# C-04_CPU_PWR.net
KiCad netlist of a schematic drawn in Altium Designer
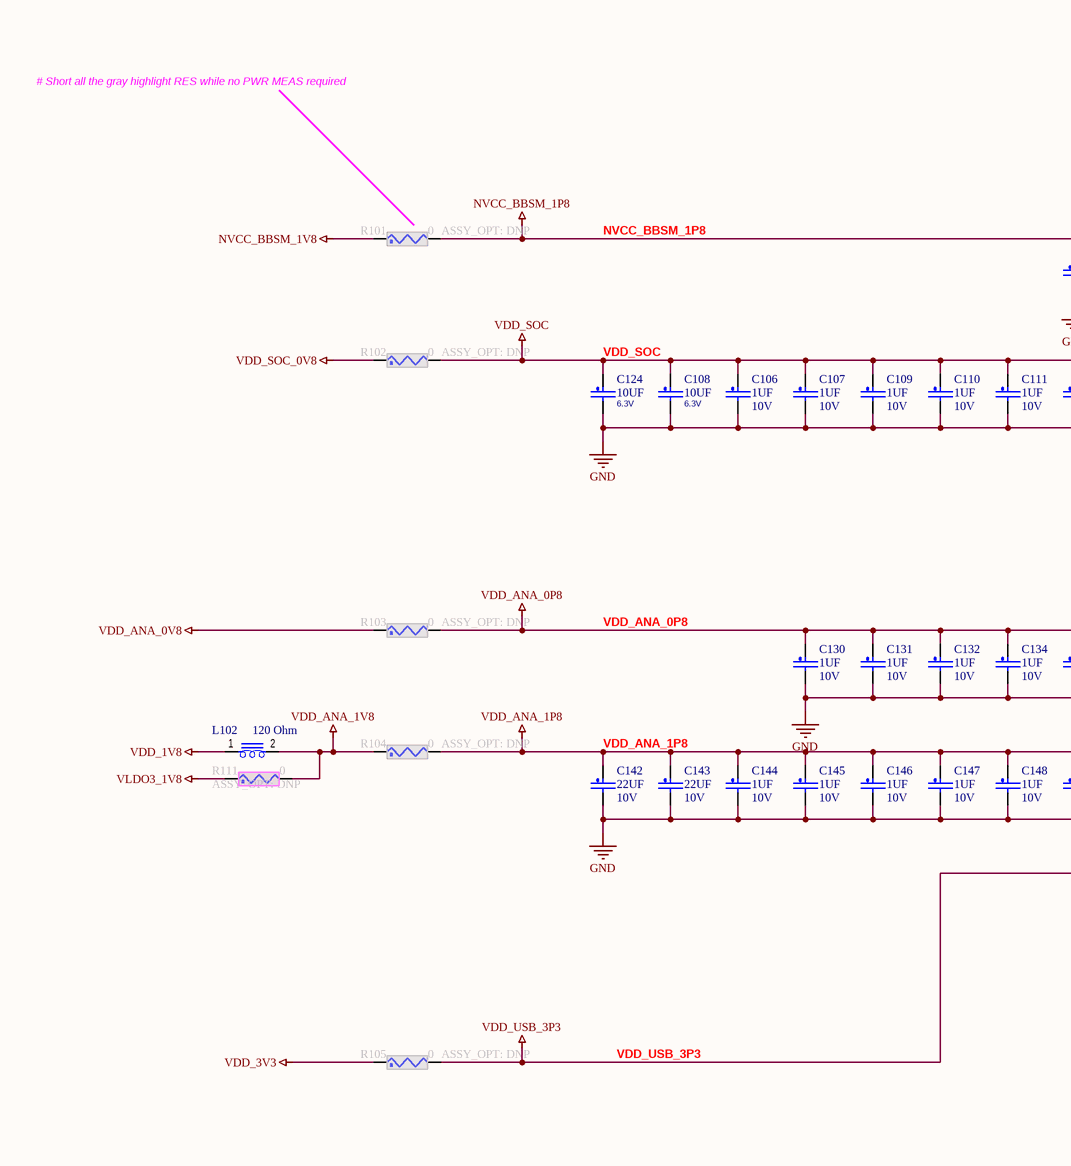
[diagram p0: C-04 CPU PWR.SchDoc, left]
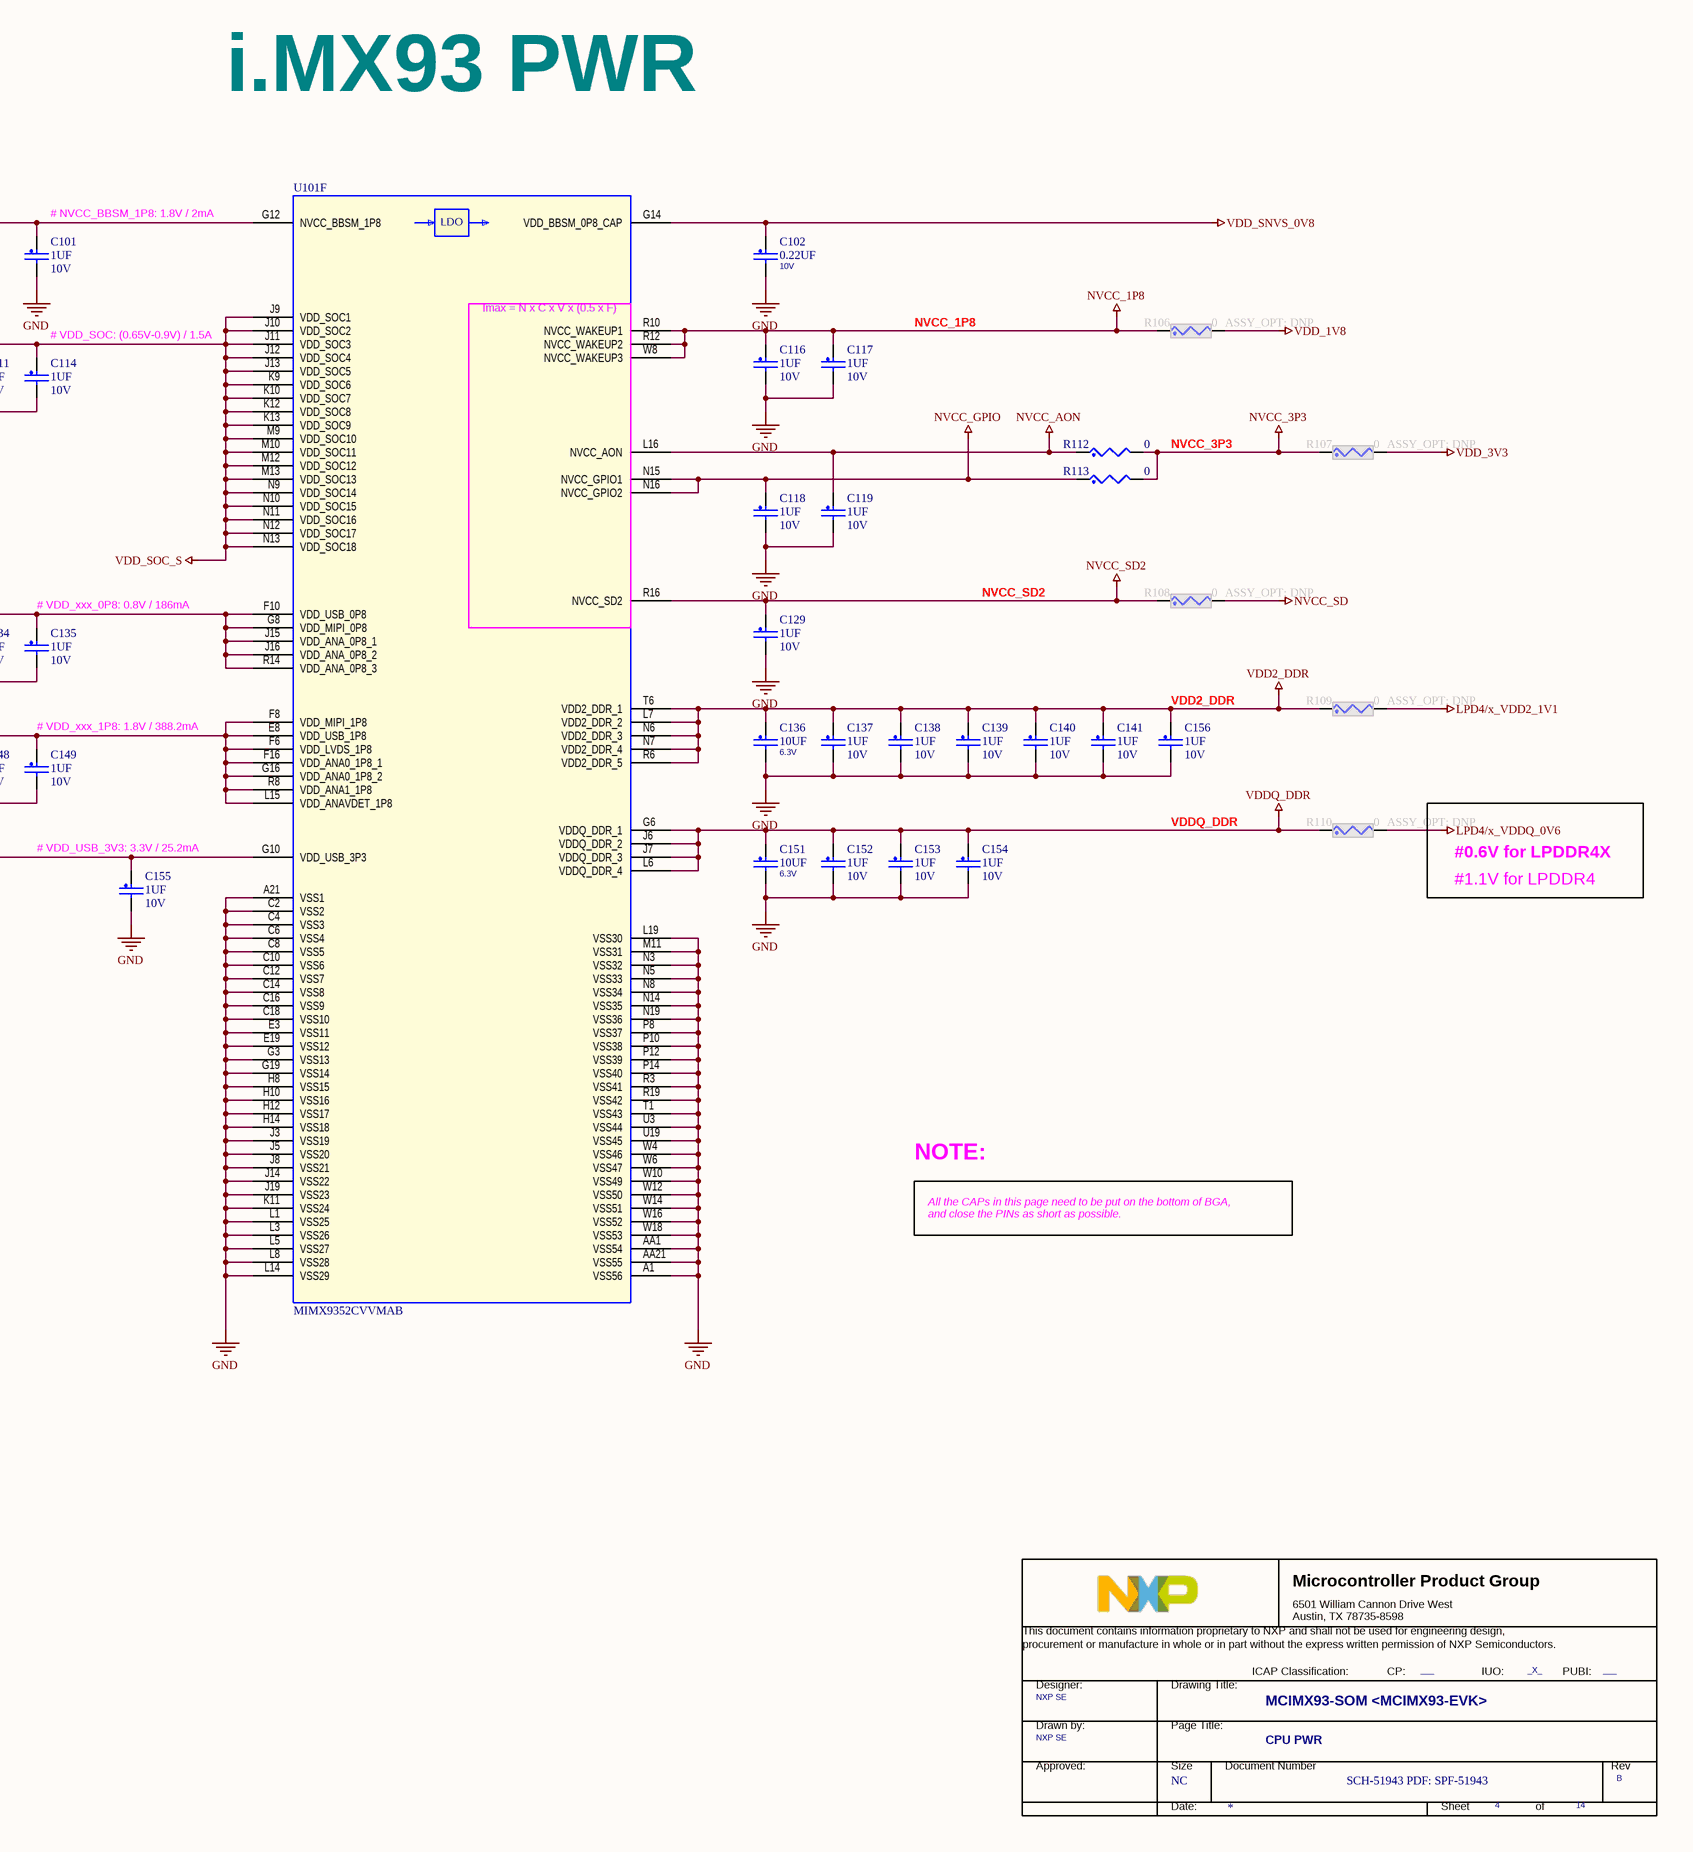
[diagram p1: C-04 CPU PWR.SchDoc, right]

(export (version "E")
  (design (tool "Eeschema 10.0.6"))
  (components
    (comp (ref "C101")
      (value "1UF")
      (footprint "0201_CC")
      (description "CAP CER 1.0uF 10V 10% X5R 0201")
      (fields (field (name "VOLTAGE") "10V") (field (name "TOLERANCE") "10%"))
      (libsource (lib "*") (part "CAP_NP"))
    )
    (comp (ref "C102")
      (value "0.22UF")
      (footprint "0201_CC")
      (description "CAP CER 0.22UF 10V 20% X5R 0201")
      (fields (field (name "TOLERANCE") "20%") (field (name "VOLTAGE") "10V"))
      (libsource (lib "*") (part "CAP_NP"))
    )
    (comp (ref "C106")
      (value "1UF")
      (footprint "0201_CC")
      (description "CAP CER 1.0uF 10V 10% X5R 0201")
      (fields (field (name "VOLTAGE") "10V") (field (name "TOLERANCE") "10%"))
      (libsource (lib "*") (part "CAP_NP"))
    )
    (comp (ref "C107")
      (value "1UF")
      (footprint "0201_CC")
      (description "CAP CER 1.0uF 10V 10% X5R 0201")
      (fields (field (name "VOLTAGE") "10V") (field (name "TOLERANCE") "10%"))
      (libsource (lib "*") (part "CAP_NP"))
    )
    (comp (ref "C108")
      (value "10UF")
      (footprint "0402_CC")
      (description "CAP CER 10UF 6.3V 20% X5R 0402")
      (fields (field (name "TOLERANCE") "20%") (field (name "VOLTAGE") "6.3V"))
      (libsource (lib "*") (part "CAP_NP"))
    )
    (comp (ref "C109")
      (value "1UF")
      (footprint "0201_CC")
      (description "CAP CER 1.0uF 10V 10% X5R 0201")
      (fields (field (name "VOLTAGE") "10V") (field (name "TOLERANCE") "10%"))
      (libsource (lib "*") (part "CAP_NP"))
    )
    (comp (ref "C110")
      (value "1UF")
      (footprint "0201_CC")
      (description "CAP CER 1.0uF 10V 10% X5R 0201")
      (fields (field (name "TOLERANCE") "10%") (field (name "VOLTAGE") "10V"))
      (libsource (lib "*") (part "CAP_NP"))
    )
    (comp (ref "C111")
      (value "1UF")
      (footprint "0201_CC")
      (description "CAP CER 1.0uF 10V 10% X5R 0201")
      (fields (field (name "TOLERANCE") "10%") (field (name "VOLTAGE") "10V"))
      (libsource (lib "*") (part "CAP_NP"))
    )
    (comp (ref "C114")
      (value "1UF")
      (footprint "0201_CC")
      (description "CAP CER 1.0uF 10V 10% X5R 0201")
      (fields (field (name "VOLTAGE") "10V") (field (name "TOLERANCE") "10%"))
      (libsource (lib "*") (part "CAP_NP"))
    )
    (comp (ref "C116")
      (value "1UF")
      (footprint "0201_CC")
      (description "CAP CER 1.0uF 10V 10% X5R 0201")
      (fields (field (name "VOLTAGE") "10V") (field (name "TOLERANCE") "10%"))
      (libsource (lib "*") (part "CAP_NP"))
    )
    (comp (ref "C117")
      (value "1UF")
      (footprint "0201_CC")
      (description "CAP CER 1.0uF 10V 10% X5R 0201")
      (fields (field (name "VOLTAGE") "10V") (field (name "TOLERANCE") "10%"))
      (libsource (lib "*") (part "CAP_NP"))
    )
    (comp (ref "C118")
      (value "1UF")
      (footprint "0201_CC")
      (description "CAP CER 1.0uF 10V 10% X5R 0201")
      (fields (field (name "VOLTAGE") "10V") (field (name "TOLERANCE") "10%"))
      (libsource (lib "*") (part "CAP_NP"))
    )
    (comp (ref "C119")
      (value "1UF")
      (footprint "0201_CC")
      (description "CAP CER 1.0uF 10V 10% X5R 0201")
      (fields (field (name "VOLTAGE") "10V") (field (name "TOLERANCE") "10%"))
      (libsource (lib "*") (part "CAP_NP"))
    )
    (comp (ref "C124")
      (value "10UF")
      (footprint "0402_CC")
      (description "CAP CER 10UF 6.3V 20% X5R 0402")
      (fields (field (name "TOLERANCE") "20%") (field (name "VOLTAGE") "6.3V"))
      (libsource (lib "*") (part "CAP_NP"))
    )
    (comp (ref "C129")
      (value "1UF")
      (footprint "0201_CC")
      (description "CAP CER 1.0uF 10V 10% X5R 0201")
      (fields (field (name "TOLERANCE") "10%") (field (name "VOLTAGE") "10V"))
      (libsource (lib "*") (part "CAP_NP"))
    )
    (comp (ref "C130")
      (value "1UF")
      (footprint "0201_CC")
      (description "CAP CER 1.0uF 10V 10% X5R 0201")
      (fields (field (name "VOLTAGE") "10V") (field (name "TOLERANCE") "10%"))
      (libsource (lib "*") (part "CAP_NP"))
    )
    (comp (ref "C131")
      (value "1UF")
      (footprint "0201_CC")
      (description "CAP CER 1.0uF 10V 10% X5R 0201")
      (fields (field (name "VOLTAGE") "10V") (field (name "TOLERANCE") "10%"))
      (libsource (lib "*") (part "CAP_NP"))
    )
    (comp (ref "C132")
      (value "1UF")
      (footprint "0201_CC")
      (description "CAP CER 1.0uF 10V 10% X5R 0201")
      (fields (field (name "VOLTAGE") "10V") (field (name "TOLERANCE") "10%"))
      (libsource (lib "*") (part "CAP_NP"))
    )
    (comp (ref "C134")
      (value "1UF")
      (footprint "0201_CC")
      (description "CAP CER 1.0uF 10V 10% X5R 0201")
      (fields (field (name "TOLERANCE") "10%") (field (name "VOLTAGE") "10V"))
      (libsource (lib "*") (part "CAP_NP"))
    )
    (comp (ref "C135")
      (value "1UF")
      (footprint "0201_CC")
      (description "CAP CER 1.0uF 10V 10% X5R 0201")
      (fields (field (name "TOLERANCE") "10%") (field (name "VOLTAGE") "10V"))
      (libsource (lib "*") (part "CAP_NP"))
    )
    (comp (ref "C136")
      (value "10UF")
      (footprint "0402_CC")
      (description "CAP CER 10UF 6.3V 20% X5R 0402")
      (fields (field (name "TOLERANCE") "20%") (field (name "VOLTAGE") "6.3V"))
      (libsource (lib "*") (part "CAP_NP"))
    )
    (comp (ref "C137")
      (value "1UF")
      (footprint "0201_CC")
      (description "CAP CER 1.0uF 10V 10% X5R 0201")
      (fields (field (name "TOLERANCE") "10%") (field (name "VOLTAGE") "10V"))
      (libsource (lib "*") (part "CAP_NP"))
    )
    (comp (ref "C138")
      (value "1UF")
      (footprint "0201_CC")
      (description "CAP CER 1.0uF 10V 10% X5R 0201")
      (fields (field (name "TOLERANCE") "10%") (field (name "VOLTAGE") "10V"))
      (libsource (lib "*") (part "CAP_NP"))
    )
    (comp (ref "C139")
      (value "1UF")
      (footprint "0201_CC")
      (description "CAP CER 1.0uF 10V 10% X5R 0201")
      (fields (field (name "TOLERANCE") "10%") (field (name "VOLTAGE") "10V"))
      (libsource (lib "*") (part "CAP_NP"))
    )
    (comp (ref "C140")
      (value "1UF")
      (footprint "0201_CC")
      (description "CAP CER 1.0uF 10V 10% X5R 0201")
      (fields (field (name "TOLERANCE") "10%") (field (name "VOLTAGE") "10V"))
      (libsource (lib "*") (part "CAP_NP"))
    )
    (comp (ref "C141")
      (value "1UF")
      (footprint "0201_CC")
      (description "CAP CER 1.0uF 10V 10% X5R 0201")
      (fields (field (name "TOLERANCE") "10%") (field (name "VOLTAGE") "10V"))
      (libsource (lib "*") (part "CAP_NP"))
    )
    (comp (ref "C142")
      (value "22UF")
      (footprint "CC0603")
      (description "CAP CER 22uF 10V 20% X5R 0603")
      (fields (field (name "VOLTAGE") "10V") (field (name "TOLERANCE") "20%"))
      (libsource (lib "*") (part "CAP_NP"))
    )
    (comp (ref "C143")
      (value "22UF")
      (footprint "CC0603")
      (description "CAP CER 22uF 10V 20% X5R 0603")
      (fields (field (name "TOLERANCE") "20%") (field (name "VOLTAGE") "10V"))
      (libsource (lib "*") (part "CAP_NP"))
    )
    (comp (ref "C144")
      (value "1UF")
      (footprint "0201_CC")
      (description "CAP CER 1.0uF 10V 10% X5R 0201")
      (fields (field (name "TOLERANCE") "10%") (field (name "VOLTAGE") "10V"))
      (libsource (lib "*") (part "CAP_NP"))
    )
    (comp (ref "C145")
      (value "1UF")
      (footprint "0201_CC")
      (description "CAP CER 1.0uF 10V 10% X5R 0201")
      (fields (field (name "VOLTAGE") "10V") (field (name "TOLERANCE") "10%"))
      (libsource (lib "*") (part "CAP_NP"))
    )
    (comp (ref "C146")
      (value "1UF")
      (footprint "0201_CC")
      (description "CAP CER 1.0uF 10V 10% X5R 0201")
      (fields (field (name "VOLTAGE") "10V") (field (name "TOLERANCE") "10%"))
      (libsource (lib "*") (part "CAP_NP"))
    )
    (comp (ref "C147")
      (value "1UF")
      (footprint "0201_CC")
      (description "CAP CER 1.0uF 10V 10% X5R 0201")
      (fields (field (name "TOLERANCE") "10%") (field (name "VOLTAGE") "10V"))
      (libsource (lib "*") (part "CAP_NP"))
    )
    (comp (ref "C148")
      (value "1UF")
      (footprint "0201_CC")
      (description "CAP CER 1.0uF 10V 10% X5R 0201")
      (fields (field (name "VOLTAGE") "10V") (field (name "TOLERANCE") "10%"))
      (libsource (lib "*") (part "CAP_NP"))
    )
    (comp (ref "C149")
      (value "1UF")
      (footprint "0201_CC")
      (description "CAP CER 1.0uF 10V 10% X5R 0201")
      (fields (field (name "VOLTAGE") "10V") (field (name "TOLERANCE") "10%"))
      (libsource (lib "*") (part "CAP_NP"))
    )
    (comp (ref "C151")
      (value "10UF")
      (footprint "0402_CC")
      (description "CAP CER 10UF 6.3V 20% X5R 0402")
      (fields (field (name "VOLTAGE") "6.3V") (field (name "TOLERANCE") "20%"))
      (libsource (lib "*") (part "CAP_NP"))
    )
    (comp (ref "C152")
      (value "1UF")
      (footprint "0201_CC")
      (description "CAP CER 1.0uF 10V 10% X5R 0201")
      (fields (field (name "VOLTAGE") "10V") (field (name "TOLERANCE") "10%"))
      (libsource (lib "*") (part "CAP_NP"))
    )
    (comp (ref "C153")
      (value "1UF")
      (footprint "0201_CC")
      (description "CAP CER 1.0uF 10V 10% X5R 0201")
      (fields (field (name "VOLTAGE") "10V") (field (name "TOLERANCE") "10%"))
      (libsource (lib "*") (part "CAP_NP"))
    )
    (comp (ref "C154")
      (value "1UF")
      (footprint "0201_CC")
      (description "CAP CER 1.0uF 10V 10% X5R 0201")
      (fields (field (name "VOLTAGE") "10V") (field (name "TOLERANCE") "10%"))
      (libsource (lib "*") (part "CAP_NP"))
    )
    (comp (ref "C155")
      (value "1UF")
      (footprint "0201_CC")
      (description "CAP CER 1.0uF 10V 10% X5R 0201")
      (fields (field (name "TOLERANCE") "10%") (field (name "VOLTAGE") "10V"))
      (libsource (lib "*") (part "CAP_NP"))
    )
    (comp (ref "C156")
      (value "1UF")
      (footprint "0201_CC")
      (description "CAP CER 1.0uF 10V 10% X5R 0201")
      (fields (field (name "VOLTAGE") "10V") (field (name "TOLERANCE") "10%"))
      (libsource (lib "*") (part "CAP_NP"))
    )
    (comp (ref "L102")
      (value "120 Ohm")
      (footprint "IND_0603")
      (description "IND FER BEAD 120OHM@100MHZ 2A 25% 0603")
      (libsource (lib "*") (part "BEAD_0"))
    )
    (comp (ref "R101")
      (value "0")
      (footprint "0402_CC")
      (description "RES MF ZERO OHM 1/16W 5% 0402")
      (fields
        (field (name "ASSY_OPT") "DNP")
        (field (name "TOLERANCE") "5%")
        (field (name "VOLTAGE") "1/16W")
      )
      (libsource (lib "*") (part "RES"))
    )
    (comp (ref "R102")
      (value "0")
      (footprint "RC0805_OV")
      (description "RES MF ZERO OHM 1/8W -- 0805")
      (fields (field (name "ASSY_OPT") "DNP") (field (name "TOLERANCE") "5%"))
      (libsource (lib "*") (part "RES"))
    )
    (comp (ref "R103")
      (value "0")
      (footprint "0603_CC")
      (description "RES MF ZERO OHM 1/10W -- 0603")
      (fields (field (name "ASSY_OPT") "DNP"))
      (libsource (lib "*") (part "RES"))
    )
    (comp (ref "R104")
      (value "0")
      (footprint "0603_CC")
      (description "RES MF ZERO OHM 1/10W -- 0603")
      (fields (field (name "ASSY_OPT") "DNP"))
      (libsource (lib "*") (part "RES"))
    )
    (comp (ref "R105")
      (value "0")
      (footprint "0402_CC")
      (description "RES MF ZERO OHM 1/16W 5% 0402")
      (fields
        (field (name "ASSY_OPT") "DNP")
        (field (name "TOLERANCE") "5%")
        (field (name "VOLTAGE") "1/16W")
      )
      (libsource (lib "*") (part "RES"))
    )
    (comp (ref "R106")
      (value "0")
      (footprint "0402_CC")
      (description "RES MF ZERO OHM 1/16W 5% 0402")
      (fields
        (field (name "ASSY_OPT") "DNP")
        (field (name "TOLERANCE") "5%")
        (field (name "VOLTAGE") "1/16W")
      )
      (libsource (lib "*") (part "RES"))
    )
    (comp (ref "R107")
      (value "0")
      (footprint "0402_CC")
      (description "RES MF ZERO OHM 1/16W 5% 0402")
      (fields
        (field (name "ASSY_OPT") "DNP")
        (field (name "TOLERANCE") "5%")
        (field (name "VOLTAGE") "1/16W")
      )
      (libsource (lib "*") (part "RES"))
    )
    (comp (ref "R108")
      (value "0")
      (footprint "0402_CC")
      (description "RES MF ZERO OHM 1/16W 5% 0402")
      (fields
        (field (name "ASSY_OPT") "DNP")
        (field (name "TOLERANCE") "5%")
        (field (name "VOLTAGE") "1/16W")
      )
      (libsource (lib "*") (part "RES"))
    )
    (comp (ref "R109")
      (value "0")
      (footprint "0603_CC")
      (description "RES MF ZERO OHM 1/10W -- 0603")
      (fields (field (name "ASSY_OPT") "DNP"))
      (libsource (lib "*") (part "RES"))
    )
    (comp (ref "R110")
      (value "0")
      (footprint "0603_CC")
      (description "RES MF ZERO OHM 1/10W -- 0603")
      (fields (field (name "ASSY_OPT") "DNP"))
      (libsource (lib "*") (part "RES"))
    )
    (comp (ref "R111")
      (value "0")
      (footprint "0603_CC")
      (description "RES MF ZERO OHM 1/10W -- 0603")
      (fields (field (name "ASSY_OPT") "DNP"))
      (libsource (lib "*") (part "RES"))
    )
    (comp (ref "R112")
      (value "0")
      (footprint "0402_CC")
      (description "RES MF ZERO OHM 1/16W 5% 0402")
      (fields (field (name "TOLERANCE") "5%") (field (name "VOLTAGE") "1/16W"))
      (libsource (lib "*") (part "RES"))
    )
    (comp (ref "R113")
      (value "0")
      (footprint "0402_CC")
      (description "RES MF ZERO OHM 1/16W 5% 0402")
      (fields (field (name "TOLERANCE") "5%") (field (name "VOLTAGE") "1/16W"))
      (libsource (lib "*") (part "RES"))
    )
    (comp (ref "U101")
      (value "MIMX9352CVVMAB")
      (footprint "SKT_BGA306_0P5_SQ16P23_ELAST")
      (description "SUBASSEMBLY SKT 306 BGA ELASTOMER SMT 0.5MM 395H AU + IC CPU 1.7GHz -- FCBGA306")
      (libsource (lib "*") (part "MIMX9352DVNxLAA"))
    )
  )
  (nets
    (net (code "1") (name "GND") (class "Default")
      (node (ref "C101") (pin "2") (pinfunction "2_2") (pintype "passive"))
      (node (ref "C102") (pin "2") (pinfunction "2_2") (pintype "passive"))
      (node (ref "C106") (pin "2") (pinfunction "2_2") (pintype "passive"))
      (node (ref "C107") (pin "2") (pinfunction "2_2") (pintype "passive"))
      (node (ref "C108") (pin "2") (pinfunction "2_2") (pintype "passive"))
      (node (ref "C109") (pin "2") (pinfunction "2_2") (pintype "passive"))
      (node (ref "C110") (pin "2") (pinfunction "2_2") (pintype "passive"))
      (node (ref "C111") (pin "2") (pinfunction "2_2") (pintype "passive"))
      (node (ref "C114") (pin "2") (pinfunction "2_2") (pintype "passive"))
      (node (ref "C116") (pin "2") (pinfunction "2_2") (pintype "passive"))
      (node (ref "C117") (pin "2") (pinfunction "2_2") (pintype "passive"))
      (node (ref "C118") (pin "2") (pinfunction "2_2") (pintype "passive"))
      (node (ref "C119") (pin "2") (pinfunction "2_2") (pintype "passive"))
      (node (ref "C124") (pin "2") (pinfunction "2_2") (pintype "passive"))
      (node (ref "C129") (pin "2") (pinfunction "2_2") (pintype "passive"))
      (node (ref "C130") (pin "2") (pinfunction "2_2") (pintype "passive"))
      (node (ref "C131") (pin "2") (pinfunction "2_2") (pintype "passive"))
      (node (ref "C132") (pin "2") (pinfunction "2_2") (pintype "passive"))
      (node (ref "C134") (pin "2") (pinfunction "2_2") (pintype "passive"))
      (node (ref "C135") (pin "2") (pinfunction "2_2") (pintype "passive"))
      (node (ref "C136") (pin "2") (pinfunction "2_2") (pintype "passive"))
      (node (ref "C137") (pin "2") (pinfunction "2_2") (pintype "passive"))
      (node (ref "C138") (pin "2") (pinfunction "2_2") (pintype "passive"))
      (node (ref "C139") (pin "2") (pinfunction "2_2") (pintype "passive"))
      (node (ref "C140") (pin "2") (pinfunction "2_2") (pintype "passive"))
      (node (ref "C141") (pin "2") (pinfunction "2_2") (pintype "passive"))
      (node (ref "C142") (pin "2") (pinfunction "2_2") (pintype "passive"))
      (node (ref "C143") (pin "2") (pinfunction "2_2") (pintype "passive"))
      (node (ref "C144") (pin "2") (pinfunction "2_2") (pintype "passive"))
      (node (ref "C145") (pin "2") (pinfunction "2_2") (pintype "passive"))
      (node (ref "C146") (pin "2") (pinfunction "2_2") (pintype "passive"))
      (node (ref "C147") (pin "2") (pinfunction "2_2") (pintype "passive"))
      (node (ref "C148") (pin "2") (pinfunction "2_2") (pintype "passive"))
      (node (ref "C149") (pin "2") (pinfunction "2_2") (pintype "passive"))
      (node (ref "C151") (pin "2") (pinfunction "2_2") (pintype "passive"))
      (node (ref "C152") (pin "2") (pinfunction "2_2") (pintype "passive"))
      (node (ref "C153") (pin "2") (pinfunction "2_2") (pintype "passive"))
      (node (ref "C154") (pin "2") (pinfunction "2_2") (pintype "passive"))
      (node (ref "C155") (pin "2") (pinfunction "2_2") (pintype "passive"))
      (node (ref "C156") (pin "2") (pinfunction "2_2") (pintype "passive"))
      (node (ref "U101") (pin "A1") (pinfunction "VSS56_A1") (pintype "passive"))
      (node (ref "U101") (pin "A21") (pinfunction "VSS1_A21") (pintype "passive"))
      (node (ref "U101") (pin "AA1") (pinfunction "VSS54_AA1") (pintype "passive"))
      (node (ref "U101") (pin "AA21") (pinfunction "VSS55_AA21") (pintype "passive"))
      (node (ref "U101") (pin "C10") (pinfunction "VSS6_C10") (pintype "passive"))
      (node (ref "U101") (pin "C12") (pinfunction "VSS7_C12") (pintype "passive"))
      (node (ref "U101") (pin "C14") (pinfunction "VSS8_C14") (pintype "passive"))
      (node (ref "U101") (pin "C16") (pinfunction "VSS9_C16") (pintype "passive"))
      (node (ref "U101") (pin "C18") (pinfunction "VSS10_C18") (pintype "passive"))
      (node (ref "U101") (pin "C2") (pinfunction "VSS2_C2") (pintype "passive"))
      (node (ref "U101") (pin "C4") (pinfunction "VSS3_C4") (pintype "passive"))
      (node (ref "U101") (pin "C6") (pinfunction "VSS4_C6") (pintype "passive"))
      (node (ref "U101") (pin "C8") (pinfunction "VSS5_C8") (pintype "passive"))
      (node (ref "U101") (pin "E19") (pinfunction "VSS12_E19") (pintype "passive"))
      (node (ref "U101") (pin "E3") (pinfunction "VSS11_E3") (pintype "passive"))
      (node (ref "U101") (pin "G19") (pinfunction "VSS14_G19") (pintype "passive"))
      (node (ref "U101") (pin "G3") (pinfunction "VSS13_G3") (pintype "passive"))
      (node (ref "U101") (pin "H10") (pinfunction "VSS16_H10") (pintype "passive"))
      (node (ref "U101") (pin "H12") (pinfunction "VSS17_H12") (pintype "passive"))
      (node (ref "U101") (pin "H14") (pinfunction "VSS18_H14") (pintype "passive"))
      (node (ref "U101") (pin "H8") (pinfunction "VSS15_H8") (pintype "passive"))
      (node (ref "U101") (pin "J14") (pinfunction "VSS22_J14") (pintype "passive"))
      (node (ref "U101") (pin "J19") (pinfunction "VSS23_J19") (pintype "passive"))
      (node (ref "U101") (pin "J3") (pinfunction "VSS19_J3") (pintype "passive"))
      (node (ref "U101") (pin "J5") (pinfunction "VSS20_J5") (pintype "passive"))
      (node (ref "U101") (pin "J8") (pinfunction "VSS21_J8") (pintype "passive"))
      (node (ref "U101") (pin "K11") (pinfunction "VSS24_K11") (pintype "passive"))
      (node (ref "U101") (pin "L1") (pinfunction "VSS25_L1") (pintype "passive"))
      (node (ref "U101") (pin "L14") (pinfunction "VSS29_L14") (pintype "passive"))
      (node (ref "U101") (pin "L19") (pinfunction "VSS30_L19") (pintype "passive"))
      (node (ref "U101") (pin "L3") (pinfunction "VSS26_L3") (pintype "passive"))
      (node (ref "U101") (pin "L5") (pinfunction "VSS27_L5") (pintype "passive"))
      (node (ref "U101") (pin "L8") (pinfunction "VSS28_L8") (pintype "passive"))
      (node (ref "U101") (pin "M11") (pinfunction "VSS31_M11") (pintype "passive"))
      (node (ref "U101") (pin "N14") (pinfunction "VSS35_N14") (pintype "passive"))
      (node (ref "U101") (pin "N19") (pinfunction "VSS36_N19") (pintype "passive"))
      (node (ref "U101") (pin "N3") (pinfunction "VSS32_N3") (pintype "passive"))
      (node (ref "U101") (pin "N5") (pinfunction "VSS33_N5") (pintype "passive"))
      (node (ref "U101") (pin "N8") (pinfunction "VSS34_N8") (pintype "passive"))
      (node (ref "U101") (pin "P10") (pinfunction "VSS38_P10") (pintype "passive"))
      (node (ref "U101") (pin "P12") (pinfunction "VSS39_P12") (pintype "passive"))
      (node (ref "U101") (pin "P14") (pinfunction "VSS40_P14") (pintype "passive"))
      (node (ref "U101") (pin "P8") (pinfunction "VSS37_P8") (pintype "passive"))
      (node (ref "U101") (pin "R19") (pinfunction "VSS42_R19") (pintype "passive"))
      (node (ref "U101") (pin "R3") (pinfunction "VSS41_R3") (pintype "passive"))
      (node (ref "U101") (pin "T1") (pinfunction "VSS43_T1") (pintype "passive"))
      (node (ref "U101") (pin "U19") (pinfunction "VSS45_U19") (pintype "passive"))
      (node (ref "U101") (pin "U3") (pinfunction "VSS44_U3") (pintype "passive"))
      (node (ref "U101") (pin "W10") (pinfunction "VSS49_W10") (pintype "passive"))
      (node (ref "U101") (pin "W12") (pinfunction "VSS50_W12") (pintype "passive"))
      (node (ref "U101") (pin "W14") (pinfunction "VSS51_W14") (pintype "passive"))
      (node (ref "U101") (pin "W16") (pinfunction "VSS52_W16") (pintype "passive"))
      (node (ref "U101") (pin "W18") (pinfunction "VSS53_W18") (pintype "passive"))
      (node (ref "U101") (pin "W4") (pinfunction "VSS46_W4") (pintype "passive"))
      (node (ref "U101") (pin "W6") (pinfunction "VSS47_W6") (pintype "passive"))
    )
    (net (code "2") (name "LPD4{slash}x_VDD2_1V1") (class "Default")
      (node (ref "R109") (pin "2") (pinfunction "2_2") (pintype "passive"))
    )
    (net (code "3") (name "LPD4{slash}x_VDDQ_0V6") (class "Default")
      (node (ref "R110") (pin "2") (pinfunction "2_2") (pintype "passive"))
    )
    (net (code "4") (name "NVCC_1P8") (class "Default")
      (node (ref "C116") (pin "1") (pinfunction "1_1") (pintype "passive"))
      (node (ref "C117") (pin "1") (pinfunction "1_1") (pintype "passive"))
      (node (ref "R106") (pin "1") (pinfunction "1_1") (pintype "passive"))
      (node (ref "U101") (pin "R10") (pinfunction "NVCC_WAKEUP1_R10") (pintype "passive"))
      (node (ref "U101") (pin "R12") (pinfunction "NVCC_WAKEUP2_R12") (pintype "passive"))
      (node (ref "U101") (pin "W8") (pinfunction "NVCC_WAKEUP3_W8") (pintype "passive"))
    )
    (net (code "5") (name "NVCC_3P3") (class "Default")
      (node (ref "R107") (pin "1") (pinfunction "1_1") (pintype "passive"))
      (node (ref "R112") (pin "2") (pinfunction "2_2") (pintype "passive"))
      (node (ref "R113") (pin "2") (pinfunction "2_2") (pintype "passive"))
    )
    (net (code "6") (name "NVCC_AON") (class "Default")
      (node (ref "C119") (pin "1") (pinfunction "1_1") (pintype "passive"))
      (node (ref "R112") (pin "1") (pinfunction "1_1") (pintype "passive"))
      (node (ref "U101") (pin "L16") (pinfunction "NVCC_AON_L16") (pintype "passive"))
    )
    (net (code "7") (name "NVCC_BBSM_1P8") (class "Default")
      (node (ref "C101") (pin "1") (pinfunction "1_1") (pintype "passive"))
      (node (ref "R101") (pin "2") (pinfunction "2_2") (pintype "passive"))
      (node (ref "U101") (pin "G12") (pinfunction "NVCC_BBSM_1P8_G12") (pintype "passive"))
    )
    (net (code "8") (name "NVCC_BBSM_1V8") (class "Default")
      (node (ref "R101") (pin "1") (pinfunction "1_1") (pintype "passive"))
    )
    (net (code "9") (name "NVCC_GPIO") (class "Default")
      (node (ref "C118") (pin "1") (pinfunction "1_1") (pintype "passive"))
      (node (ref "R113") (pin "1") (pinfunction "1_1") (pintype "passive"))
      (node (ref "U101") (pin "N15") (pinfunction "NVCC_GPIO1_N15") (pintype "passive"))
      (node (ref "U101") (pin "N16") (pinfunction "NVCC_GPIO2_N16") (pintype "passive"))
    )
    (net (code "10") (name "NVCC_SD") (class "Default")
      (node (ref "R108") (pin "2") (pinfunction "2_2") (pintype "passive"))
    )
    (net (code "11") (name "NVCC_SD2") (class "Default")
      (node (ref "C129") (pin "1") (pinfunction "1_1") (pintype "passive"))
      (node (ref "R108") (pin "1") (pinfunction "1_1") (pintype "passive"))
      (node (ref "U101") (pin "R16") (pinfunction "NVCC_SD2_R16") (pintype "passive"))
    )
    (net (code "12") (name "VDD2_DDR") (class "Default")
      (node (ref "C136") (pin "1") (pinfunction "1_1") (pintype "passive"))
      (node (ref "C137") (pin "1") (pinfunction "1_1") (pintype "passive"))
      (node (ref "C138") (pin "1") (pinfunction "1_1") (pintype "passive"))
      (node (ref "C139") (pin "1") (pinfunction "1_1") (pintype "passive"))
      (node (ref "C140") (pin "1") (pinfunction "1_1") (pintype "passive"))
      (node (ref "C141") (pin "1") (pinfunction "1_1") (pintype "passive"))
      (node (ref "C156") (pin "1") (pinfunction "1_1") (pintype "passive"))
      (node (ref "R109") (pin "1") (pinfunction "1_1") (pintype "passive"))
      (node (ref "U101") (pin "L7") (pinfunction "VDD2_DDR_2_L7") (pintype "passive"))
      (node (ref "U101") (pin "N6") (pinfunction "VDD2_DDR_3_N6") (pintype "passive"))
      (node (ref "U101") (pin "N7") (pinfunction "VDD2_DDR_4_N7") (pintype "passive"))
      (node (ref "U101") (pin "R6") (pinfunction "VDD2_DDR_5_R6") (pintype "passive"))
      (node (ref "U101") (pin "T6") (pinfunction "VDD2_DDR_1_T6") (pintype "passive"))
    )
    (net (code "13") (name "VDDQ_DDR") (class "Default")
      (node (ref "C151") (pin "1") (pinfunction "1_1") (pintype "passive"))
      (node (ref "C152") (pin "1") (pinfunction "1_1") (pintype "passive"))
      (node (ref "C153") (pin "1") (pinfunction "1_1") (pintype "passive"))
      (node (ref "C154") (pin "1") (pinfunction "1_1") (pintype "passive"))
      (node (ref "R110") (pin "1") (pinfunction "1_1") (pintype "passive"))
      (node (ref "U101") (pin "G6") (pinfunction "VDDQ_DDR_1_G6") (pintype "passive"))
      (node (ref "U101") (pin "J6") (pinfunction "VDDQ_DDR_2_J6") (pintype "passive"))
      (node (ref "U101") (pin "J7") (pinfunction "VDDQ_DDR_3_J7") (pintype "passive"))
      (node (ref "U101") (pin "L6") (pinfunction "VDDQ_DDR_4_L6") (pintype "passive"))
    )
    (net (code "14") (name "VDD_1V8") (class "Default")
      (node (ref "L102") (pin "1") (pinfunction "1_1") (pintype "passive"))
      (node (ref "R106") (pin "2") (pinfunction "2_2") (pintype "passive"))
    )
    (net (code "15") (name "VDD_3V3") (class "Default")
      (node (ref "R105") (pin "1") (pinfunction "1_1") (pintype "passive"))
      (node (ref "R107") (pin "2") (pinfunction "2_2") (pintype "passive"))
    )
    (net (code "16") (name "VDD_ANA_0P8") (class "Default")
      (node (ref "C130") (pin "1") (pinfunction "1_1") (pintype "passive"))
      (node (ref "C131") (pin "1") (pinfunction "1_1") (pintype "passive"))
      (node (ref "C132") (pin "1") (pinfunction "1_1") (pintype "passive"))
      (node (ref "C134") (pin "1") (pinfunction "1_1") (pintype "passive"))
      (node (ref "C135") (pin "1") (pinfunction "1_1") (pintype "passive"))
      (node (ref "R103") (pin "2") (pinfunction "2_2") (pintype "passive"))
      (node (ref "U101") (pin "F10") (pinfunction "VDD_USB_0P8_F10") (pintype "passive"))
      (node (ref "U101") (pin "G8") (pinfunction "VDD_MIPI_0P8_G8") (pintype "passive"))
      (node (ref "U101") (pin "J15") (pinfunction "VDD_ANA_0P8_1_J15") (pintype "passive"))
      (node (ref "U101") (pin "J16") (pinfunction "VDD_ANA_0P8_2_J16") (pintype "passive"))
      (node (ref "U101") (pin "R14") (pinfunction "VDD_ANA_0P8_3_R14") (pintype "passive"))
    )
    (net (code "17") (name "VDD_ANA_0V8") (class "Default")
      (node (ref "R103") (pin "1") (pinfunction "1_1") (pintype "passive"))
    )
    (net (code "18") (name "VDD_ANA_1P8") (class "Default")
      (node (ref "C142") (pin "1") (pinfunction "1_1") (pintype "passive"))
      (node (ref "C143") (pin "1") (pinfunction "1_1") (pintype "passive"))
      (node (ref "C144") (pin "1") (pinfunction "1_1") (pintype "passive"))
      (node (ref "C145") (pin "1") (pinfunction "1_1") (pintype "passive"))
      (node (ref "C146") (pin "1") (pinfunction "1_1") (pintype "passive"))
      (node (ref "C147") (pin "1") (pinfunction "1_1") (pintype "passive"))
      (node (ref "C148") (pin "1") (pinfunction "1_1") (pintype "passive"))
      (node (ref "C149") (pin "1") (pinfunction "1_1") (pintype "passive"))
      (node (ref "R104") (pin "2") (pinfunction "2_2") (pintype "passive"))
      (node (ref "U101") (pin "E8") (pinfunction "VDD_USB_1P8_E8") (pintype "passive"))
      (node (ref "U101") (pin "F16") (pinfunction "VDD_ANA0_1P8_1_F16") (pintype "passive"))
      (node (ref "U101") (pin "F6") (pinfunction "VDD_LVDS_1P8_F6") (pintype "passive"))
      (node (ref "U101") (pin "F8") (pinfunction "VDD_MIPI_1P8_F8") (pintype "passive"))
      (node (ref "U101") (pin "G16") (pinfunction "VDD_ANA0_1P8_2_G16") (pintype "passive"))
      (node (ref "U101") (pin "L15") (pinfunction "VDD_ANAVDET_1P8_L15") (pintype "passive"))
      (node (ref "U101") (pin "R8") (pinfunction "VDD_ANA1_1P8_R8") (pintype "passive"))
    )
    (net (code "19") (name "VDD_ANA_1V8") (class "Default")
      (node (ref "L102") (pin "2") (pinfunction "2_2") (pintype "passive"))
      (node (ref "R104") (pin "1") (pinfunction "1_1") (pintype "passive"))
      (node (ref "R111") (pin "2") (pinfunction "2_2") (pintype "passive"))
    )
    (net (code "20") (name "VDD_SNVS_0V8") (class "Default")
      (node (ref "C102") (pin "1") (pinfunction "1_1") (pintype "passive"))
      (node (ref "U101") (pin "G14") (pinfunction "VDD_BBSM_0P8_CAP_G14") (pintype "passive"))
    )
    (net (code "21") (name "VDD_SOC") (class "Default")
      (node (ref "C106") (pin "1") (pinfunction "1_1") (pintype "passive"))
      (node (ref "C107") (pin "1") (pinfunction "1_1") (pintype "passive"))
      (node (ref "C108") (pin "1") (pinfunction "1_1") (pintype "passive"))
      (node (ref "C109") (pin "1") (pinfunction "1_1") (pintype "passive"))
      (node (ref "C110") (pin "1") (pinfunction "1_1") (pintype "passive"))
      (node (ref "C111") (pin "1") (pinfunction "1_1") (pintype "passive"))
      (node (ref "C114") (pin "1") (pinfunction "1_1") (pintype "passive"))
      (node (ref "C124") (pin "1") (pinfunction "1_1") (pintype "passive"))
      (node (ref "R102") (pin "2") (pinfunction "2_2") (pintype "passive"))
      (node (ref "U101") (pin "J10") (pinfunction "VDD_SOC2_J10") (pintype "passive"))
      (node (ref "U101") (pin "J11") (pinfunction "VDD_SOC3_J11") (pintype "passive"))
      (node (ref "U101") (pin "J12") (pinfunction "VDD_SOC4_J12") (pintype "passive"))
      (node (ref "U101") (pin "J13") (pinfunction "VDD_SOC5_J13") (pintype "passive"))
      (node (ref "U101") (pin "J9") (pinfunction "VDD_SOC1_J9") (pintype "passive"))
      (node (ref "U101") (pin "K10") (pinfunction "VDD_SOC7_K10") (pintype "passive"))
      (node (ref "U101") (pin "K12") (pinfunction "VDD_SOC8_K12") (pintype "passive"))
      (node (ref "U101") (pin "K13") (pinfunction "VDD_SOC9_K13") (pintype "passive"))
      (node (ref "U101") (pin "K9") (pinfunction "VDD_SOC6_K9") (pintype "passive"))
      (node (ref "U101") (pin "M10") (pinfunction "VDD_SOC11_M10") (pintype "passive"))
      (node (ref "U101") (pin "M12") (pinfunction "VDD_SOC12_M12") (pintype "passive"))
      (node (ref "U101") (pin "M13") (pinfunction "VDD_SOC13_M13") (pintype "passive"))
      (node (ref "U101") (pin "M9") (pinfunction "VDD_SOC10_M9") (pintype "passive"))
      (node (ref "U101") (pin "N10") (pinfunction "VDD_SOC15_N10") (pintype "passive"))
      (node (ref "U101") (pin "N11") (pinfunction "VDD_SOC16_N11") (pintype "passive"))
      (node (ref "U101") (pin "N12") (pinfunction "VDD_SOC17_N12") (pintype "passive"))
      (node (ref "U101") (pin "N13") (pinfunction "VDD_SOC18_N13") (pintype "passive"))
      (node (ref "U101") (pin "N9") (pinfunction "VDD_SOC14_N9") (pintype "passive"))
    )
    (net (code "22") (name "VDD_SOC_0V8") (class "Default")
      (node (ref "R102") (pin "1") (pinfunction "1_1") (pintype "passive"))
    )
    (net (code "23") (name "VDD_USB_3P3") (class "Default")
      (node (ref "C155") (pin "1") (pinfunction "1_1") (pintype "passive"))
      (node (ref "R105") (pin "2") (pinfunction "2_2") (pintype "passive"))
      (node (ref "U101") (pin "G10") (pinfunction "VDD_USB_3P3_G10") (pintype "passive"))
    )
    (net (code "24") (name "VLDO3_1V8") (class "Default")
      (node (ref "R111") (pin "1") (pinfunction "1_1") (pintype "passive"))
    )
  )
)
